# APP_1_ADC_m.net
KiCad netlist of a schematic drawn in Altium Designer
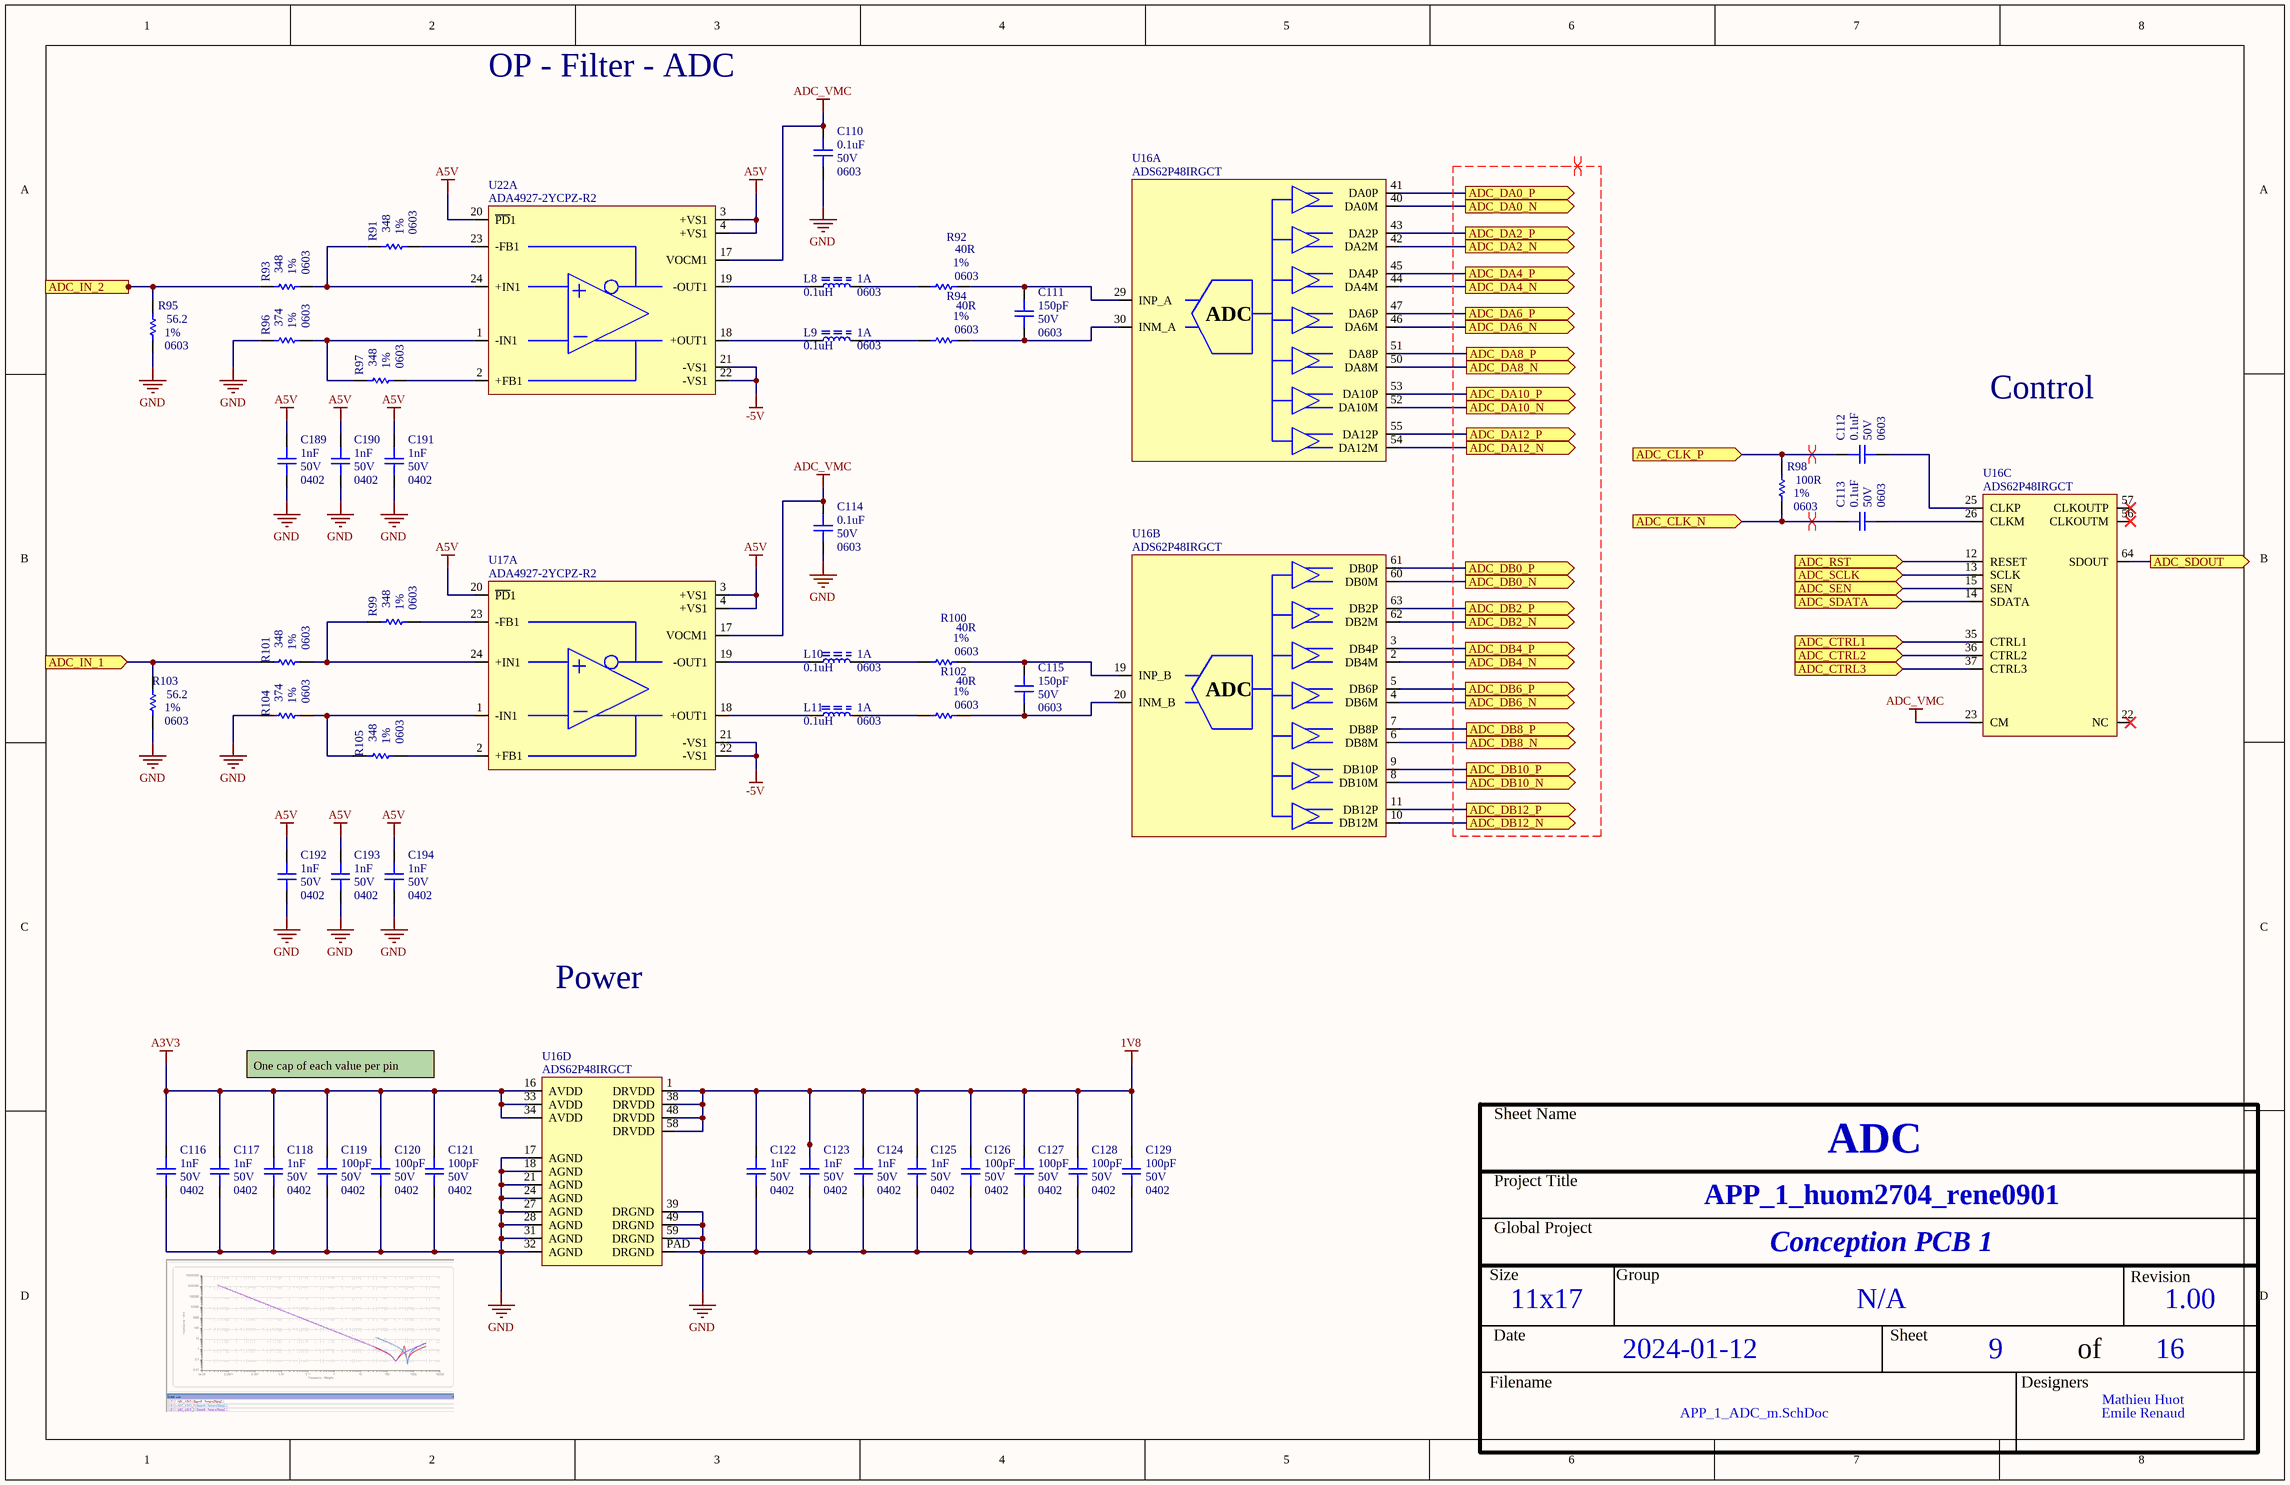
[diagram p0: APP_1_ADC_m.SchDoc]

(export (version "E")
  (design (tool "Eeschema 10.0.6"))
  (components
    (comp (ref "C110")
      (value "0.1uF")
      (footprint "CAP_0603")
      (description "CAP - 0603")
      (fields
        (field (name "VOLTAGE") "50V")
        (field (name "PACKAGE") "0603")
        (field (name "CREATEDBY") "Jonathan Bouchard")
      )
      (libsource (lib "S7CAS_LIB2023") (part "CAP - 0603"))
    )
    (comp (ref "C111")
      (value "150pF")
      (footprint "CAP_0603")
      (description "CAP - 0603")
      (fields
        (field (name "VOLTAGE") "50V")
        (field (name "PACKAGE") "0603")
        (field (name "CREATEDBY") "Jonathan Bouchard")
      )
      (libsource (lib "S7CAS_LIB2023") (part "CAP - 0603"))
    )
    (comp (ref "C112")
      (value "0.1uF")
      (footprint "CAP_0603")
      (description "CAP - 0603")
      (fields
        (field (name "VOLTAGE") "50V")
        (field (name "PACKAGE") "0603")
        (field (name "CREATEDBY") "Jonathan Bouchard")
      )
      (libsource (lib "S7CAS_LIB2023") (part "CAP - 0603"))
    )
    (comp (ref "C113")
      (value "0.1uF")
      (footprint "CAP_0603")
      (description "CAP - 0603")
      (fields
        (field (name "VOLTAGE") "50V")
        (field (name "PACKAGE") "0603")
        (field (name "CREATEDBY") "Jonathan Bouchard")
      )
      (libsource (lib "S7CAS_LIB2023") (part "CAP - 0603"))
    )
    (comp (ref "C114")
      (value "0.1uF")
      (footprint "CAP_0603")
      (description "CAP - 0603")
      (fields
        (field (name "VOLTAGE") "50V")
        (field (name "PACKAGE") "0603")
        (field (name "CREATEDBY") "Jonathan Bouchard")
      )
      (libsource (lib "S7CAS_LIB2023") (part "CAP - 0603"))
    )
    (comp (ref "C115")
      (value "150pF")
      (footprint "CAP_0603")
      (description "CAP - 0603")
      (fields
        (field (name "VOLTAGE") "50V")
        (field (name "PACKAGE") "0603")
        (field (name "CREATEDBY") "Jonathan Bouchard")
      )
      (libsource (lib "S7CAS_LIB2023") (part "CAP - 0603"))
    )
    (comp (ref "C116")
      (value "1nF")
      (footprint "CAP_0402")
      (description "CAP - 0402")
      (fields
        (field (name "VOLTAGE") "50V")
        (field (name "PACKAGE") "0402")
        (field (name "CREATEDBY") "Jonathan Bouchard")
      )
      (libsource (lib "S7CAS_LIB2023") (part "CAP - 0402"))
    )
    (comp (ref "C117")
      (value "1nF")
      (footprint "CAP_0402")
      (description "CAP - 0402")
      (fields
        (field (name "VOLTAGE") "50V")
        (field (name "PACKAGE") "0402")
        (field (name "CREATEDBY") "Jonathan Bouchard")
      )
      (libsource (lib "S7CAS_LIB2023") (part "CAP - 0402"))
    )
    (comp (ref "C118")
      (value "1nF")
      (footprint "CAP_0402")
      (description "CAP - 0402")
      (fields
        (field (name "VOLTAGE") "50V")
        (field (name "PACKAGE") "0402")
        (field (name "CREATEDBY") "Jonathan Bouchard")
      )
      (libsource (lib "S7CAS_LIB2023") (part "CAP - 0402"))
    )
    (comp (ref "C119")
      (value "100pF")
      (footprint "CAP_0402")
      (description "CAP - 0402")
      (fields
        (field (name "VOLTAGE") "50V")
        (field (name "PACKAGE") "0402")
        (field (name "CREATEDBY") "Jonathan Bouchard")
      )
      (libsource (lib "S7CAS_LIB2023") (part "CAP - 0402"))
    )
    (comp (ref "C120")
      (value "100pF")
      (footprint "CAP_0402")
      (description "CAP - 0402")
      (fields
        (field (name "VOLTAGE") "50V")
        (field (name "PACKAGE") "0402")
        (field (name "CREATEDBY") "Jonathan Bouchard")
      )
      (libsource (lib "S7CAS_LIB2023") (part "CAP - 0402"))
    )
    (comp (ref "C121")
      (value "100pF")
      (footprint "CAP_0402")
      (description "CAP - 0402")
      (fields
        (field (name "VOLTAGE") "50V")
        (field (name "PACKAGE") "0402")
        (field (name "CREATEDBY") "Jonathan Bouchard")
      )
      (libsource (lib "S7CAS_LIB2023") (part "CAP - 0402"))
    )
    (comp (ref "C122")
      (value "1nF")
      (footprint "CAP_0402")
      (description "CAP - 0402")
      (fields
        (field (name "VOLTAGE") "50V")
        (field (name "PACKAGE") "0402")
        (field (name "CREATEDBY") "Jonathan Bouchard")
      )
      (libsource (lib "S7CAS_LIB2023") (part "CAP - 0402"))
    )
    (comp (ref "C123")
      (value "1nF")
      (footprint "CAP_0402")
      (description "CAP - 0402")
      (fields
        (field (name "VOLTAGE") "50V")
        (field (name "PACKAGE") "0402")
        (field (name "CREATEDBY") "Jonathan Bouchard")
      )
      (libsource (lib "S7CAS_LIB2023") (part "CAP - 0402"))
    )
    (comp (ref "C124")
      (value "1nF")
      (footprint "CAP_0402")
      (description "CAP - 0402")
      (fields
        (field (name "VOLTAGE") "50V")
        (field (name "PACKAGE") "0402")
        (field (name "CREATEDBY") "Jonathan Bouchard")
      )
      (libsource (lib "S7CAS_LIB2023") (part "CAP - 0402"))
    )
    (comp (ref "C125")
      (value "1nF")
      (footprint "CAP_0402")
      (description "CAP - 0402")
      (fields
        (field (name "VOLTAGE") "50V")
        (field (name "PACKAGE") "0402")
        (field (name "CREATEDBY") "Jonathan Bouchard")
      )
      (libsource (lib "S7CAS_LIB2023") (part "CAP - 0402"))
    )
    (comp (ref "C126")
      (value "100pF")
      (footprint "CAP_0402")
      (description "CAP - 0402")
      (fields
        (field (name "VOLTAGE") "50V")
        (field (name "PACKAGE") "0402")
        (field (name "CREATEDBY") "Jonathan Bouchard")
      )
      (libsource (lib "S7CAS_LIB2023") (part "CAP - 0402"))
    )
    (comp (ref "C127")
      (value "100pF")
      (footprint "CAP_0402")
      (description "CAP - 0402")
      (fields
        (field (name "VOLTAGE") "50V")
        (field (name "PACKAGE") "0402")
        (field (name "CREATEDBY") "Jonathan Bouchard")
      )
      (libsource (lib "S7CAS_LIB2023") (part "CAP - 0402"))
    )
    (comp (ref "C128")
      (value "100pF")
      (footprint "CAP_0402")
      (description "CAP - 0402")
      (fields
        (field (name "VOLTAGE") "50V")
        (field (name "PACKAGE") "0402")
        (field (name "CREATEDBY") "Jonathan Bouchard")
      )
      (libsource (lib "S7CAS_LIB2023") (part "CAP - 0402"))
    )
    (comp (ref "C129")
      (value "100pF")
      (footprint "CAP_0402")
      (description "CAP - 0402")
      (fields
        (field (name "VOLTAGE") "50V")
        (field (name "PACKAGE") "0402")
        (field (name "CREATEDBY") "Jonathan Bouchard")
      )
      (libsource (lib "S7CAS_LIB2023") (part "CAP - 0402"))
    )
    (comp (ref "C189")
      (value "1nF")
      (footprint "CAP_0402")
      (description "CAP - 0402")
      (fields
        (field (name "VOLTAGE") "50V")
        (field (name "PACKAGE") "0402")
        (field (name "CREATEDBY") "Jonathan Bouchard")
      )
      (libsource (lib "S7CAS_LIB2023") (part "CAP - 0402"))
    )
    (comp (ref "C190")
      (value "1nF")
      (footprint "CAP_0402")
      (description "CAP - 0402")
      (fields
        (field (name "VOLTAGE") "50V")
        (field (name "PACKAGE") "0402")
        (field (name "CREATEDBY") "Jonathan Bouchard")
      )
      (libsource (lib "S7CAS_LIB2023") (part "CAP - 0402"))
    )
    (comp (ref "C191")
      (value "1nF")
      (footprint "CAP_0402")
      (description "CAP - 0402")
      (fields
        (field (name "VOLTAGE") "50V")
        (field (name "PACKAGE") "0402")
        (field (name "CREATEDBY") "Jonathan Bouchard")
      )
      (libsource (lib "S7CAS_LIB2023") (part "CAP - 0402"))
    )
    (comp (ref "C192")
      (value "1nF")
      (footprint "CAP_0402")
      (description "CAP - 0402")
      (fields
        (field (name "VOLTAGE") "50V")
        (field (name "PACKAGE") "0402")
        (field (name "CREATEDBY") "Jonathan Bouchard")
      )
      (libsource (lib "S7CAS_LIB2023") (part "CAP - 0402"))
    )
    (comp (ref "C193")
      (value "1nF")
      (footprint "CAP_0402")
      (description "CAP - 0402")
      (fields
        (field (name "VOLTAGE") "50V")
        (field (name "PACKAGE") "0402")
        (field (name "CREATEDBY") "Jonathan Bouchard")
      )
      (libsource (lib "S7CAS_LIB2023") (part "CAP - 0402"))
    )
    (comp (ref "C194")
      (value "1nF")
      (footprint "CAP_0402")
      (description "CAP - 0402")
      (fields
        (field (name "VOLTAGE") "50V")
        (field (name "PACKAGE") "0402")
        (field (name "CREATEDBY") "Jonathan Bouchard")
      )
      (libsource (lib "S7CAS_LIB2023") (part "CAP - 0402"))
    )
    (comp (ref "L8")
      (value "0.1uH")
      (footprint "FER_0603")
      (description "FER - 0603")
      (fields
        (field (name "CURRENT") "1A")
        (field (name "PACKAGE") "0603")
        (field (name "CREATEDBY") "Jonathan Bouchard")
      )
      (libsource (lib "S7CAS_LIB2023") (part "FER - 0603"))
    )
    (comp (ref "L9")
      (value "0.1uH")
      (footprint "FER_0603")
      (description "FER - 0603")
      (fields
        (field (name "CURRENT") "1A")
        (field (name "PACKAGE") "0603")
        (field (name "CREATEDBY") "Jonathan Bouchard")
      )
      (libsource (lib "S7CAS_LIB2023") (part "FER - 0603"))
    )
    (comp (ref "L10")
      (value "0.1uH")
      (footprint "FER_0603")
      (description "FER - 0603")
      (fields
        (field (name "CURRENT") "1A")
        (field (name "PACKAGE") "0603")
        (field (name "CREATEDBY") "Jonathan Bouchard")
      )
      (libsource (lib "S7CAS_LIB2023") (part "FER - 0603"))
    )
    (comp (ref "L11")
      (value "0.1uH")
      (footprint "FER_0603")
      (description "FER - 0603")
      (fields
        (field (name "CURRENT") "1A")
        (field (name "PACKAGE") "0603")
        (field (name "CREATEDBY") "Jonathan Bouchard")
      )
      (libsource (lib "S7CAS_LIB2023") (part "FER - 0603"))
    )
    (comp (ref "R91")
      (value "348")
      (footprint "RES_0603")
      (description "RES - 0603")
      (fields
        (field (name "PACKAGE") "0603")
        (field (name "PRECISION") "1%")
        (field (name "CREATEDBY") "Jonathan Bouchard")
      )
      (libsource (lib "S7CAS_LIB2023") (part "RES - 0603"))
    )
    (comp (ref "R92")
      (value "40R")
      (footprint "RES_0603")
      (description "RES - 0603")
      (fields
        (field (name "PACKAGE") "0603")
        (field (name "PRECISION") "1%")
        (field (name "CREATEDBY") "Jonathan Bouchard")
      )
      (libsource (lib "S7CAS_LIB2023") (part "RES - 0603"))
    )
    (comp (ref "R93")
      (value "348")
      (footprint "RES_0603")
      (description "RES - 0603")
      (fields
        (field (name "PACKAGE") "0603")
        (field (name "PRECISION") "1%")
        (field (name "CREATEDBY") "Jonathan Bouchard")
      )
      (libsource (lib "S7CAS_LIB2023") (part "RES - 0603"))
    )
    (comp (ref "R94")
      (value "40R")
      (footprint "RES_0603")
      (description "RES - 0603")
      (fields
        (field (name "PACKAGE") "0603")
        (field (name "PRECISION") "1%")
        (field (name "CREATEDBY") "Jonathan Bouchard")
      )
      (libsource (lib "S7CAS_LIB2023") (part "RES - 0603"))
    )
    (comp (ref "R95")
      (value "56.2")
      (footprint "RES_0603")
      (description "RES - 0603")
      (fields
        (field (name "PACKAGE") "0603")
        (field (name "PRECISION") "1%")
        (field (name "CREATEDBY") "Jonathan Bouchard")
      )
      (libsource (lib "S7CAS_LIB2023") (part "RES - 0603"))
    )
    (comp (ref "R96")
      (value "374")
      (footprint "RES_0603")
      (description "RES - 0603")
      (fields
        (field (name "PACKAGE") "0603")
        (field (name "PRECISION") "1%")
        (field (name "CREATEDBY") "Jonathan Bouchard")
      )
      (libsource (lib "S7CAS_LIB2023") (part "RES - 0603"))
    )
    (comp (ref "R97")
      (value "348")
      (footprint "RES_0603")
      (description "RES - 0603")
      (fields
        (field (name "PACKAGE") "0603")
        (field (name "PRECISION") "1%")
        (field (name "CREATEDBY") "Jonathan Bouchard")
      )
      (libsource (lib "S7CAS_LIB2023") (part "RES - 0603"))
    )
    (comp (ref "R98")
      (value "100R")
      (footprint "RES_0603")
      (description "RES - 0603")
      (fields
        (field (name "PACKAGE") "0603")
        (field (name "PRECISION") "1%")
        (field (name "CREATEDBY") "Jonathan Bouchard")
      )
      (libsource (lib "S7CAS_LIB2023") (part "RES - 0603"))
    )
    (comp (ref "R99")
      (value "348")
      (footprint "RES_0603")
      (description "RES - 0603")
      (fields
        (field (name "PACKAGE") "0603")
        (field (name "PRECISION") "1%")
        (field (name "CREATEDBY") "Jonathan Bouchard")
      )
      (libsource (lib "S7CAS_LIB2023") (part "RES - 0603"))
    )
    (comp (ref "R100")
      (value "40R")
      (footprint "RES_0603")
      (description "RES - 0603")
      (fields
        (field (name "PACKAGE") "0603")
        (field (name "PRECISION") "1%")
        (field (name "CREATEDBY") "Jonathan Bouchard")
      )
      (libsource (lib "S7CAS_LIB2023") (part "RES - 0603"))
    )
    (comp (ref "R101")
      (value "348")
      (footprint "RES_0603")
      (description "RES - 0603")
      (fields
        (field (name "PACKAGE") "0603")
        (field (name "PRECISION") "1%")
        (field (name "CREATEDBY") "Jonathan Bouchard")
      )
      (libsource (lib "S7CAS_LIB2023") (part "RES - 0603"))
    )
    (comp (ref "R102")
      (value "40R")
      (footprint "RES_0603")
      (description "RES - 0603")
      (fields
        (field (name "PACKAGE") "0603")
        (field (name "PRECISION") "1%")
        (field (name "CREATEDBY") "Jonathan Bouchard")
      )
      (libsource (lib "S7CAS_LIB2023") (part "RES - 0603"))
    )
    (comp (ref "R103")
      (value "56.2")
      (footprint "RES_0603")
      (description "RES - 0603")
      (fields
        (field (name "PACKAGE") "0603")
        (field (name "PRECISION") "1%")
        (field (name "CREATEDBY") "Jonathan Bouchard")
      )
      (libsource (lib "S7CAS_LIB2023") (part "RES - 0603"))
    )
    (comp (ref "R104")
      (value "374")
      (footprint "RES_0603")
      (description "RES - 0603")
      (fields
        (field (name "PACKAGE") "0603")
        (field (name "PRECISION") "1%")
        (field (name "CREATEDBY") "Jonathan Bouchard")
      )
      (libsource (lib "S7CAS_LIB2023") (part "RES - 0603"))
    )
    (comp (ref "R105")
      (value "348")
      (footprint "RES_0603")
      (description "RES - 0603")
      (fields
        (field (name "PACKAGE") "0603")
        (field (name "PRECISION") "1%")
        (field (name "CREATEDBY") "Jonathan Bouchard")
      )
      (libsource (lib "S7CAS_LIB2023") (part "RES - 0603"))
    )
    (comp (ref "U16")
      (value "ADS62P48IRGCT")
      (footprint "ADC_ADS62P48IRGCT")
      (description "ADC - 14 BIT 210MSPS SUAL - VQFN-64")
      (fields
        (field (name "VOLTAGE") "3.15 V ~ 3.6 V / 1.7 V ~ 1.9 V")
        (field (name "MFG") "Texas Instruments")
        (field (name "CREATEDBY") "Jonathan Bouchard")
      )
      (libsource (lib "S7CAS_LIB2023") (part "ADC_ADS62P48IRGCT"))
    )
    (comp (ref "U17")
      (value "ADA4927-2YCPZ-R2")
      (footprint "OPAMP_ADA4927-2YCPZ-R2")
      (description "OPAMP - CFA 2.3GHZ - QFN-24")
      (fields
        (field (name "VOLTAGE") "4.5 V ~ 11 V, ±2.25 V ~ 5.5 V")
        (field (name "MFG") "Analog Devices")
        (field (name "CREATEDBY") "Jonathan Bouchard")
      )
      (libsource (lib "S7CAS_LIB2023") (part "OPAMP_ADA4927-2YCPZ-R2"))
    )
    (comp (ref "U22")
      (value "ADA4927-2YCPZ-R2")
      (footprint "OPAMP_ADA4927-2YCPZ-R2")
      (description "OPAMP - CFA 2.3GHZ - QFN-24")
      (fields
        (field (name "VOLTAGE") "4.5 V ~ 11 V, ±2.25 V ~ 5.5 V")
        (field (name "MFG") "Analog Devices")
        (field (name "CREATEDBY") "Jonathan Bouchard")
      )
      (libsource (lib "S7CAS_LIB2023") (part "OPAMP_ADA4927-2YCPZ-R2"))
    )
  )
  (nets
    (net (code "1") (name "-5V") (class "Default")
      (node (ref "U17") (pin "21") (pinfunction "-VS1_21") (pintype "passive"))
      (node (ref "U17") (pin "22") (pinfunction "-VS1_22") (pintype "passive"))
      (node (ref "U22") (pin "21") (pinfunction "-VS1_21") (pintype "passive"))
      (node (ref "U22") (pin "22") (pinfunction "-VS1_22") (pintype "passive"))
    )
    (net (code "2") (name "/ADC_CLK_N") (class "Default")
      (node (ref "C113") (pin "2") (pinfunction "2_2") (pintype "passive"))
      (node (ref "R98") (pin "1") (pinfunction "1_1") (pintype "passive"))
    )
    (net (code "3") (name "/ADC_CLK_P") (class "Default")
      (node (ref "C112") (pin "2") (pinfunction "2_2") (pintype "passive"))
      (node (ref "R98") (pin "2") (pinfunction "2_2") (pintype "passive"))
    )
    (net (code "4") (name "/ADC_CTRL1") (class "Default")
      (node (ref "U16") (pin "35") (pinfunction "CTRL1_35") (pintype "passive"))
    )
    (net (code "5") (name "/ADC_CTRL2") (class "Default")
      (node (ref "U16") (pin "36") (pinfunction "CTRL2_36") (pintype "passive"))
    )
    (net (code "6") (name "/ADC_CTRL3") (class "Default")
      (node (ref "U16") (pin "37") (pinfunction "CTRL3_37") (pintype "passive"))
    )
    (net (code "7") (name "/ADC_DA0_N") (class "Default")
      (node (ref "U16") (pin "40") (pinfunction "DA0M_40") (pintype "passive"))
    )
    (net (code "8") (name "/ADC_DA0_P") (class "Default")
      (node (ref "U16") (pin "41") (pinfunction "DA0P_41") (pintype "passive"))
    )
    (net (code "9") (name "/ADC_DA2_N") (class "Default")
      (node (ref "U16") (pin "42") (pinfunction "DA2M_42") (pintype "passive"))
    )
    (net (code "10") (name "/ADC_DA2_P") (class "Default")
      (node (ref "U16") (pin "43") (pinfunction "DA2P_43") (pintype "passive"))
    )
    (net (code "11") (name "/ADC_DA4_N") (class "Default")
      (node (ref "U16") (pin "44") (pinfunction "DA4M_44") (pintype "passive"))
    )
    (net (code "12") (name "/ADC_DA4_P") (class "Default")
      (node (ref "U16") (pin "45") (pinfunction "DA4P_45") (pintype "passive"))
    )
    (net (code "13") (name "/ADC_DA6_N") (class "Default")
      (node (ref "U16") (pin "46") (pinfunction "DA6M_46") (pintype "passive"))
    )
    (net (code "14") (name "/ADC_DA6_P") (class "Default")
      (node (ref "U16") (pin "47") (pinfunction "DA6P_47") (pintype "passive"))
    )
    (net (code "15") (name "/ADC_DA8_N") (class "Default")
      (node (ref "U16") (pin "50") (pinfunction "DA8M_50") (pintype "passive"))
    )
    (net (code "16") (name "/ADC_DA8_P") (class "Default")
      (node (ref "U16") (pin "51") (pinfunction "DA8P_51") (pintype "passive"))
    )
    (net (code "17") (name "/ADC_DA10_N") (class "Default")
      (node (ref "U16") (pin "52") (pinfunction "DA10M_52") (pintype "passive"))
    )
    (net (code "18") (name "/ADC_DA10_P") (class "Default")
      (node (ref "U16") (pin "53") (pinfunction "DA10P_53") (pintype "passive"))
    )
    (net (code "19") (name "/ADC_DA12_N") (class "Default")
      (node (ref "U16") (pin "54") (pinfunction "DA12M_54") (pintype "passive"))
    )
    (net (code "20") (name "/ADC_DA12_P") (class "Default")
      (node (ref "U16") (pin "55") (pinfunction "DA12P_55") (pintype "passive"))
    )
    (net (code "21") (name "/ADC_DB0_N") (class "Default")
      (node (ref "U16") (pin "60") (pinfunction "DB0M_60") (pintype "passive"))
    )
    (net (code "22") (name "/ADC_DB0_P") (class "Default")
      (node (ref "U16") (pin "61") (pinfunction "DB0P_61") (pintype "passive"))
    )
    (net (code "23") (name "/ADC_DB2_N") (class "Default")
      (node (ref "U16") (pin "62") (pinfunction "DB2M_62") (pintype "passive"))
    )
    (net (code "24") (name "/ADC_DB2_P") (class "Default")
      (node (ref "U16") (pin "63") (pinfunction "DB2P_63") (pintype "passive"))
    )
    (net (code "25") (name "/ADC_DB4_N") (class "Default")
      (node (ref "U16") (pin "2") (pinfunction "DB4M_2") (pintype "passive"))
    )
    (net (code "26") (name "/ADC_DB4_P") (class "Default")
      (node (ref "U16") (pin "3") (pinfunction "DB4P_3") (pintype "passive"))
    )
    (net (code "27") (name "/ADC_DB6_N") (class "Default")
      (node (ref "U16") (pin "4") (pinfunction "DB6M_4") (pintype "passive"))
    )
    (net (code "28") (name "/ADC_DB6_P") (class "Default")
      (node (ref "U16") (pin "5") (pinfunction "DB6P_5") (pintype "passive"))
    )
    (net (code "29") (name "/ADC_DB8_N") (class "Default")
      (node (ref "U16") (pin "6") (pinfunction "DB8M_6") (pintype "passive"))
    )
    (net (code "30") (name "/ADC_DB8_P") (class "Default")
      (node (ref "U16") (pin "7") (pinfunction "DB8P_7") (pintype "passive"))
    )
    (net (code "31") (name "/ADC_DB10_N") (class "Default")
      (node (ref "U16") (pin "8") (pinfunction "DB10M_8") (pintype "passive"))
    )
    (net (code "32") (name "/ADC_DB10_P") (class "Default")
      (node (ref "U16") (pin "9") (pinfunction "DB10P_9") (pintype "passive"))
    )
    (net (code "33") (name "/ADC_DB12_N") (class "Default")
      (node (ref "U16") (pin "10") (pinfunction "DB12M_10") (pintype "passive"))
    )
    (net (code "34") (name "/ADC_DB12_P") (class "Default")
      (node (ref "U16") (pin "11") (pinfunction "DB12P_11") (pintype "passive"))
    )
    (net (code "35") (name "/ADC_IN_1") (class "Default")
      (node (ref "R101") (pin "2") (pinfunction "2_2") (pintype "passive"))
      (node (ref "R103") (pin "2") (pinfunction "2_2") (pintype "passive"))
    )
    (net (code "36") (name "/ADC_IN_2") (class "Default")
      (node (ref "R93") (pin "2") (pinfunction "2_2") (pintype "passive"))
      (node (ref "R95") (pin "2") (pinfunction "2_2") (pintype "passive"))
    )
    (net (code "37") (name "/ADC_RST") (class "Default")
      (node (ref "U16") (pin "12") (pinfunction "RESET_12") (pintype "passive"))
    )
    (net (code "38") (name "/ADC_SCLK") (class "Default")
      (node (ref "U16") (pin "13") (pinfunction "SCLK_13") (pintype "passive"))
    )
    (net (code "39") (name "/ADC_SDATA") (class "Default")
      (node (ref "U16") (pin "14") (pinfunction "SDATA_14") (pintype "passive"))
    )
    (net (code "40") (name "/ADC_SDOUT") (class "Default")
      (node (ref "U16") (pin "64") (pinfunction "SDOUT_64") (pintype "passive"))
    )
    (net (code "41") (name "/ADC_SEN") (class "Default")
      (node (ref "U16") (pin "15") (pinfunction "SEN_15") (pintype "passive"))
    )
    (net (code "42") (name "1V8") (class "Default")
      (node (ref "C122") (pin "2") (pinfunction "2_2") (pintype "passive"))
      (node (ref "C123") (pin "2") (pinfunction "2_2") (pintype "passive"))
      (node (ref "C124") (pin "2") (pinfunction "2_2") (pintype "passive"))
      (node (ref "C125") (pin "2") (pinfunction "2_2") (pintype "passive"))
      (node (ref "C126") (pin "2") (pinfunction "2_2") (pintype "passive"))
      (node (ref "C127") (pin "2") (pinfunction "2_2") (pintype "passive"))
      (node (ref "C128") (pin "2") (pinfunction "2_2") (pintype "passive"))
      (node (ref "C129") (pin "2") (pinfunction "2_2") (pintype "passive"))
      (node (ref "U16") (pin "1") (pinfunction "DRVDD_1") (pintype "passive"))
      (node (ref "U16") (pin "38") (pinfunction "DRVDD_38") (pintype "passive"))
      (node (ref "U16") (pin "48") (pinfunction "DRVDD_48") (pintype "passive"))
      (node (ref "U16") (pin "58") (pinfunction "DRVDD_58") (pintype "passive"))
    )
    (net (code "43") (name "A3V3") (class "Default")
      (node (ref "C116") (pin "2") (pinfunction "2_2") (pintype "passive"))
      (node (ref "C117") (pin "2") (pinfunction "2_2") (pintype "passive"))
      (node (ref "C118") (pin "2") (pinfunction "2_2") (pintype "passive"))
      (node (ref "C119") (pin "2") (pinfunction "2_2") (pintype "passive"))
      (node (ref "C120") (pin "2") (pinfunction "2_2") (pintype "passive"))
      (node (ref "C121") (pin "2") (pinfunction "2_2") (pintype "passive"))
      (node (ref "U16") (pin "16") (pinfunction "AVDD_16") (pintype "passive"))
      (node (ref "U16") (pin "33") (pinfunction "AVDD_33") (pintype "passive"))
      (node (ref "U16") (pin "34") (pinfunction "AVDD_34") (pintype "passive"))
    )
    (net (code "44") (name "A5V") (class "Default")
      (node (ref "C189") (pin "2") (pinfunction "2_2") (pintype "passive"))
      (node (ref "C190") (pin "2") (pinfunction "2_2") (pintype "passive"))
      (node (ref "C191") (pin "2") (pinfunction "2_2") (pintype "passive"))
      (node (ref "C192") (pin "2") (pinfunction "2_2") (pintype "passive"))
      (node (ref "C193") (pin "2") (pinfunction "2_2") (pintype "passive"))
      (node (ref "C194") (pin "2") (pinfunction "2_2") (pintype "passive"))
      (node (ref "U17") (pin "20") (pinfunction "~{PD}1_20") (pintype "passive"))
      (node (ref "U17") (pin "3") (pinfunction "+VS1_3") (pintype "passive"))
      (node (ref "U17") (pin "4") (pinfunction "+VS1_4") (pintype "passive"))
      (node (ref "U22") (pin "20") (pinfunction "~{PD}1_20") (pintype "passive"))
      (node (ref "U22") (pin "3") (pinfunction "+VS1_3") (pintype "passive"))
      (node (ref "U22") (pin "4") (pinfunction "+VS1_4") (pintype "passive"))
    )
    (net (code "45") (name "ADC_VMC") (class "Default")
      (node (ref "C110") (pin "2") (pinfunction "2_2") (pintype "passive"))
      (node (ref "C114") (pin "2") (pinfunction "2_2") (pintype "passive"))
      (node (ref "U16") (pin "23") (pinfunction "CM_23") (pintype "passive"))
      (node (ref "U17") (pin "17") (pinfunction "VOCM1_17") (pintype "passive"))
      (node (ref "U22") (pin "17") (pinfunction "VOCM1_17") (pintype "passive"))
    )
    (net (code "46") (name "GND") (class "Default")
      (node (ref "C110") (pin "1") (pinfunction "1_1") (pintype "passive"))
      (node (ref "C114") (pin "1") (pinfunction "1_1") (pintype "passive"))
      (node (ref "C116") (pin "1") (pinfunction "1_1") (pintype "passive"))
      (node (ref "C117") (pin "1") (pinfunction "1_1") (pintype "passive"))
      (node (ref "C118") (pin "1") (pinfunction "1_1") (pintype "passive"))
      (node (ref "C119") (pin "1") (pinfunction "1_1") (pintype "passive"))
      (node (ref "C120") (pin "1") (pinfunction "1_1") (pintype "passive"))
      (node (ref "C121") (pin "1") (pinfunction "1_1") (pintype "passive"))
      (node (ref "C122") (pin "1") (pinfunction "1_1") (pintype "passive"))
      (node (ref "C123") (pin "1") (pinfunction "1_1") (pintype "passive"))
      (node (ref "C124") (pin "1") (pinfunction "1_1") (pintype "passive"))
      (node (ref "C125") (pin "1") (pinfunction "1_1") (pintype "passive"))
      (node (ref "C126") (pin "1") (pinfunction "1_1") (pintype "passive"))
      (node (ref "C127") (pin "1") (pinfunction "1_1") (pintype "passive"))
      (node (ref "C128") (pin "1") (pinfunction "1_1") (pintype "passive"))
      (node (ref "C129") (pin "1") (pinfunction "1_1") (pintype "passive"))
      (node (ref "C189") (pin "1") (pinfunction "1_1") (pintype "passive"))
      (node (ref "C190") (pin "1") (pinfunction "1_1") (pintype "passive"))
      (node (ref "C191") (pin "1") (pinfunction "1_1") (pintype "passive"))
      (node (ref "C192") (pin "1") (pinfunction "1_1") (pintype "passive"))
      (node (ref "C193") (pin "1") (pinfunction "1_1") (pintype "passive"))
      (node (ref "C194") (pin "1") (pinfunction "1_1") (pintype "passive"))
      (node (ref "R103") (pin "1") (pinfunction "1_1") (pintype "passive"))
      (node (ref "R104") (pin "2") (pinfunction "2_2") (pintype "passive"))
      (node (ref "R95") (pin "1") (pinfunction "1_1") (pintype "passive"))
      (node (ref "R96") (pin "2") (pinfunction "2_2") (pintype "passive"))
      (node (ref "U16") (pin "17") (pinfunction "AGND_17") (pintype "passive"))
      (node (ref "U16") (pin "18") (pinfunction "AGND_18") (pintype "passive"))
      (node (ref "U16") (pin "21") (pinfunction "AGND_21") (pintype "passive"))
      (node (ref "U16") (pin "24") (pinfunction "AGND_24") (pintype "passive"))
      (node (ref "U16") (pin "27") (pinfunction "AGND_27") (pintype "passive"))
      (node (ref "U16") (pin "28") (pinfunction "AGND_28") (pintype "passive"))
      (node (ref "U16") (pin "31") (pinfunction "AGND_31") (pintype "passive"))
      (node (ref "U16") (pin "32") (pinfunction "AGND_32") (pintype "passive"))
      (node (ref "U16") (pin "39") (pinfunction "DRGND_39") (pintype "passive"))
      (node (ref "U16") (pin "49") (pinfunction "DRGND_49") (pintype "passive"))
      (node (ref "U16") (pin "59") (pinfunction "DRGND_59") (pintype "passive"))
      (node (ref "U16") (pin "PAD") (pinfunction "DRGND_PAD") (pintype "passive"))
    )
    (net (code "47") (name "Net-(L8-Pad1)") (class "Default")
      (node (ref "L8") (pin "1") (pinfunction "1_1") (pintype "passive"))
      (node (ref "R92") (pin "2") (pinfunction "2_2") (pintype "passive"))
    )
    (net (code "48") (name "Net-(L9-Pad1)") (class "Default")
      (node (ref "L9") (pin "1") (pinfunction "1_1") (pintype "passive"))
      (node (ref "R94") (pin "2") (pinfunction "2_2") (pintype "passive"))
    )
    (net (code "49") (name "Net-(L10-Pad1)") (class "Default")
      (node (ref "L10") (pin "1") (pinfunction "1_1") (pintype "passive"))
      (node (ref "R100") (pin "2") (pinfunction "2_2") (pintype "passive"))
    )
    (net (code "50") (name "Net-(L11-Pad1)") (class "Default")
      (node (ref "L11") (pin "1") (pinfunction "1_1") (pintype "passive"))
      (node (ref "R102") (pin "2") (pinfunction "2_2") (pintype "passive"))
    )
    (net (code "51") (name "Net-(U16A-INM_A)") (class "Default")
      (node (ref "C111") (pin "1") (pinfunction "1_1") (pintype "passive"))
      (node (ref "R94") (pin "1") (pinfunction "1_1") (pintype "passive"))
      (node (ref "U16") (pin "30") (pinfunction "INM_A_30") (pintype "passive"))
    )
    (net (code "52") (name "Net-(U16A-INP_A)") (class "Default")
      (node (ref "C111") (pin "2") (pinfunction "2_2") (pintype "passive"))
      (node (ref "R92") (pin "1") (pinfunction "1_1") (pintype "passive"))
      (node (ref "U16") (pin "29") (pinfunction "INP_A_29") (pintype "passive"))
    )
    (net (code "53") (name "Net-(U16B-INM_B)") (class "Default")
      (node (ref "C115") (pin "1") (pinfunction "1_1") (pintype "passive"))
      (node (ref "R102") (pin "1") (pinfunction "1_1") (pintype "passive"))
      (node (ref "U16") (pin "20") (pinfunction "INM_B_20") (pintype "passive"))
    )
    (net (code "54") (name "Net-(U16B-INP_B)") (class "Default")
      (node (ref "C115") (pin "2") (pinfunction "2_2") (pintype "passive"))
      (node (ref "R100") (pin "1") (pinfunction "1_1") (pintype "passive"))
      (node (ref "U16") (pin "19") (pinfunction "INP_B_19") (pintype "passive"))
    )
    (net (code "55") (name "Net-(U16C-CLKM)") (class "Default")
      (node (ref "C113") (pin "1") (pinfunction "1_1") (pintype "passive"))
      (node (ref "U16") (pin "26") (pinfunction "CLKM_26") (pintype "passive"))
    )
    (net (code "56") (name "Net-(U16C-CLKP)") (class "Default")
      (node (ref "C112") (pin "1") (pinfunction "1_1") (pintype "passive"))
      (node (ref "U16") (pin "25") (pinfunction "CLKP_25") (pintype "passive"))
    )
    (net (code "57") (name "Net-(U17A-+FB1)") (class "Default")
      (node (ref "R105") (pin "1") (pinfunction "1_1") (pintype "passive"))
      (node (ref "U17") (pin "2") (pinfunction "+FB1_2") (pintype "passive"))
    )
    (net (code "58") (name "Net-(U17A-+IN1)") (class "Default")
      (node (ref "R101") (pin "1") (pinfunction "1_1") (pintype "passive"))
      (node (ref "R99") (pin "2") (pinfunction "2_2") (pintype "passive"))
      (node (ref "U17") (pin "24") (pinfunction "+IN1_24") (pintype "passive"))
    )
    (net (code "59") (name "Net-(U17A-+OUT1)") (class "Default")
      (node (ref "L11") (pin "2") (pinfunction "2_2") (pintype "passive"))
      (node (ref "U17") (pin "18") (pinfunction "+OUT1_18") (pintype "passive"))
    )
    (net (code "60") (name "Net-(U17A--FB1)") (class "Default")
      (node (ref "R99") (pin "1") (pinfunction "1_1") (pintype "passive"))
      (node (ref "U17") (pin "23") (pinfunction "-FB1_23") (pintype "passive"))
    )
    (net (code "61") (name "Net-(U17A--IN1)") (class "Default")
      (node (ref "R104") (pin "1") (pinfunction "1_1") (pintype "passive"))
      (node (ref "R105") (pin "2") (pinfunction "2_2") (pintype "passive"))
      (node (ref "U17") (pin "1") (pinfunction "-IN1_1") (pintype "passive"))
    )
    (net (code "62") (name "Net-(U17A--OUT1)") (class "Default")
      (node (ref "L10") (pin "2") (pinfunction "2_2") (pintype "passive"))
      (node (ref "U17") (pin "19") (pinfunction "-OUT1_19") (pintype "passive"))
    )
    (net (code "63") (name "Net-(U22A-+FB1)") (class "Default")
      (node (ref "R97") (pin "1") (pinfunction "1_1") (pintype "passive"))
      (node (ref "U22") (pin "2") (pinfunction "+FB1_2") (pintype "passive"))
    )
    (net (code "64") (name "Net-(U22A-+IN1)") (class "Default")
      (node (ref "R91") (pin "2") (pinfunction "2_2") (pintype "passive"))
      (node (ref "R93") (pin "1") (pinfunction "1_1") (pintype "passive"))
      (node (ref "U22") (pin "24") (pinfunction "+IN1_24") (pintype "passive"))
    )
    (net (code "65") (name "Net-(U22A-+OUT1)") (class "Default")
      (node (ref "L9") (pin "2") (pinfunction "2_2") (pintype "passive"))
      (node (ref "U22") (pin "18") (pinfunction "+OUT1_18") (pintype "passive"))
    )
    (net (code "66") (name "Net-(U22A--FB1)") (class "Default")
      (node (ref "R91") (pin "1") (pinfunction "1_1") (pintype "passive"))
      (node (ref "U22") (pin "23") (pinfunction "-FB1_23") (pintype "passive"))
    )
    (net (code "67") (name "Net-(U22A--IN1)") (class "Default")
      (node (ref "R96") (pin "1") (pinfunction "1_1") (pintype "passive"))
      (node (ref "R97") (pin "2") (pinfunction "2_2") (pintype "passive"))
      (node (ref "U22") (pin "1") (pinfunction "-IN1_1") (pintype "passive"))
    )
    (net (code "68") (name "Net-(U22A--OUT1)") (class "Default")
      (node (ref "L8") (pin "2") (pinfunction "2_2") (pintype "passive"))
      (node (ref "U22") (pin "19") (pinfunction "-OUT1_19") (pintype "passive"))
    )
    (net (code "69") (name "unconnected-(U16C-CLKOUTM-Pad56)") (class "Default")
      (node (ref "U16") (pin "56") (pinfunction "CLKOUTM_56") (pintype "passive+no_connect"))
    )
    (net (code "70") (name "unconnected-(U16C-CLKOUTP-Pad57)") (class "Default")
      (node (ref "U16") (pin "57") (pinfunction "CLKOUTP_57") (pintype "passive+no_connect"))
    )
    (net (code "71") (name "unconnected-(U16C-NC-Pad22)") (class "Default")
      (node (ref "U16") (pin "22") (pinfunction "NC_22") (pintype "passive+no_connect"))
    )
  )
)
